# dawa_v5_5.net
KiCad netlist of a schematic drawn in EAGLE
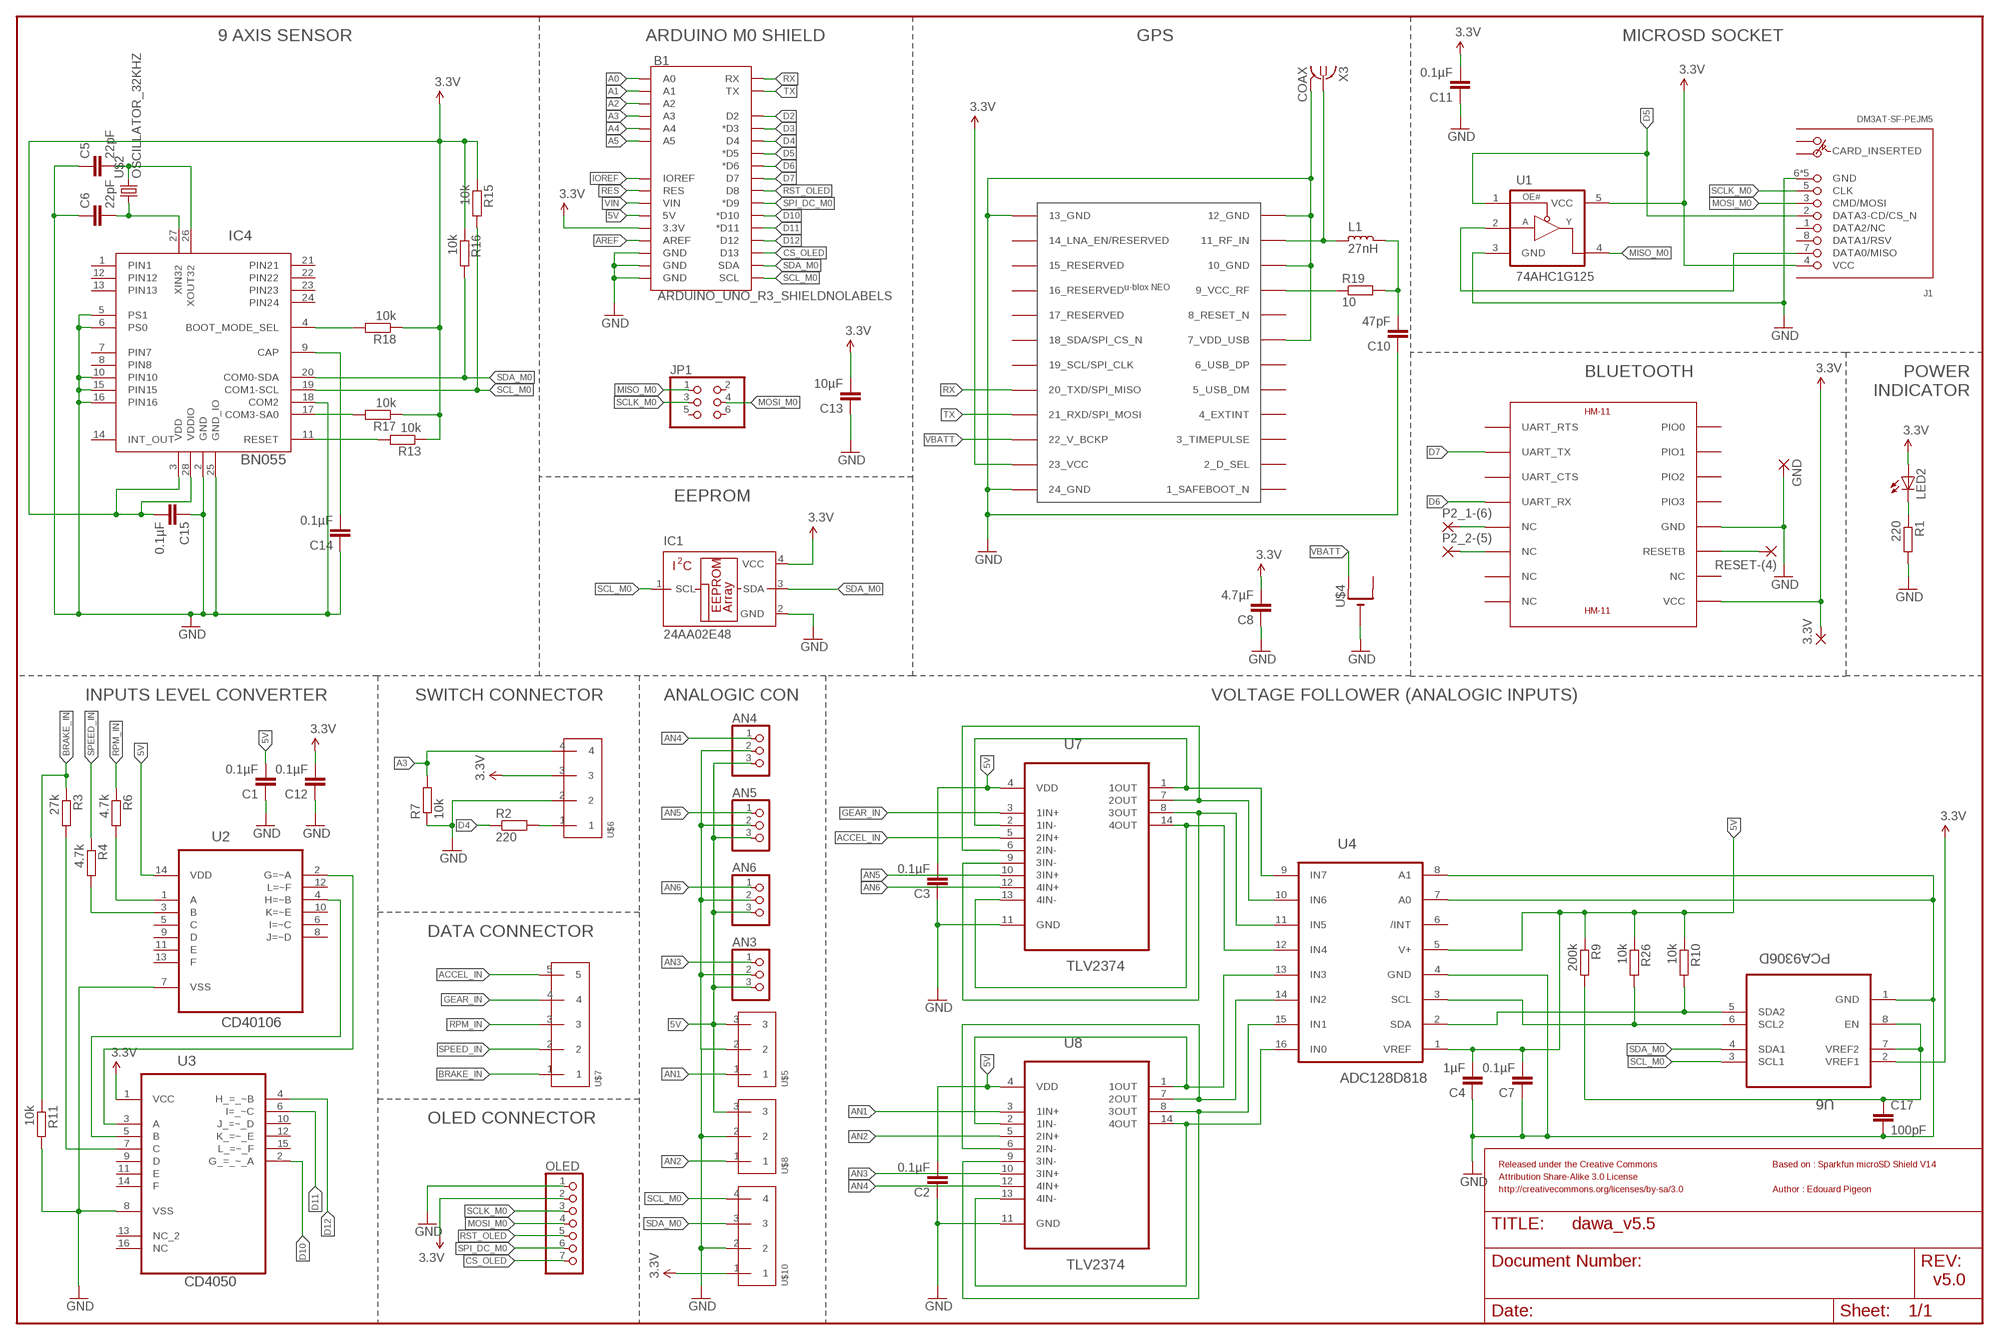
[diagram p0: schematic, sheet 1, part 1 of 2]
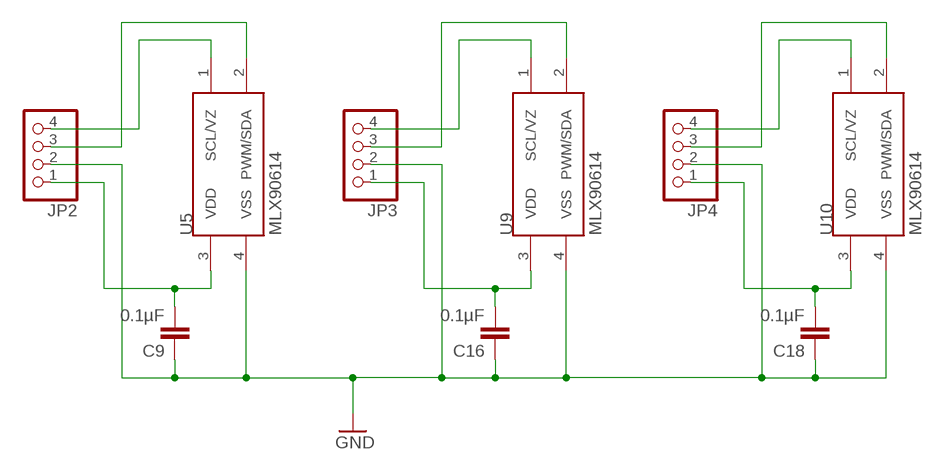
[diagram p1: schematic, sheet 1, part 2 of 2]

(export (version "E")
  (design (tool "Eeschema 10.0.6"))
  (components
    (comp (ref "3.3V")
      (value "WIREPADSMD1,27-254")
      (footprint "eagle-import:SMD1,27-2,54")
      (libsource (lib "eagle-import") (part "WIREPADSMD1,27-254"))
    )
    (comp (ref "AN3")
      (value "PINHD-1X3")
      (footprint "eagle-import:1X03")
      (libsource (lib "eagle-import") (part "PINHD-1X3"))
    )
    (comp (ref "AN4")
      (value "PINHD-1X3")
      (footprint "eagle-import:1X03")
      (libsource (lib "eagle-import") (part "PINHD-1X3"))
    )
    (comp (ref "AN5")
      (value "PINHD-1X3")
      (footprint "eagle-import:1X03")
      (libsource (lib "eagle-import") (part "PINHD-1X3"))
    )
    (comp (ref "AN6")
      (value "PINHD-1X3")
      (footprint "eagle-import:1X03")
      (libsource (lib "eagle-import") (part "PINHD-1X3"))
    )
    (comp (ref "B1")
      (value "ARDUINO_UNO_R3_SHIELDNOLABELS")
      (footprint "eagle-import:UNO_R3_SHIELD_NOLABELS")
      (libsource (lib "eagle-import") (part "ARDUINO_UNO_R3_SHIELDNOLABELS"))
    )
    (comp (ref "C1")
      (value "0.1µF")
      (footprint "eagle-import:C0603")
      (libsource (lib "eagle-import") (part "C-EUC0603"))
    )
    (comp (ref "C2")
      (value "0.1µF")
      (footprint "eagle-import:C0603")
      (libsource (lib "eagle-import") (part "C-EUC0603"))
    )
    (comp (ref "C3")
      (value "0.1µF")
      (footprint "eagle-import:C0603")
      (libsource (lib "eagle-import") (part "C-EUC0603"))
    )
    (comp (ref "C4")
      (value "1µF")
      (footprint "eagle-import:C0603")
      (libsource (lib "eagle-import") (part "C-EUC0603"))
    )
    (comp (ref "C5")
      (value "22pF")
      (footprint "eagle-import:C0603")
      (libsource (lib "eagle-import") (part "C-EUC0603"))
    )
    (comp (ref "C6")
      (value "22pF")
      (footprint "eagle-import:C0603")
      (libsource (lib "eagle-import") (part "C-EUC0603"))
    )
    (comp (ref "C7")
      (value "0.1µF")
      (footprint "eagle-import:C0603")
      (libsource (lib "eagle-import") (part "C-EUC0603"))
    )
    (comp (ref "C8")
      (value "4.7µF")
      (footprint "eagle-import:C0603")
      (libsource (lib "eagle-import") (part "C-EUC0603"))
    )
    (comp (ref "C9")
      (value "0.1µF")
      (footprint "eagle-import:C0603")
      (libsource (lib "eagle-import") (part "C-EUC0603"))
    )
    (comp (ref "C10")
      (value "47pF")
      (footprint "eagle-import:C0603")
      (libsource (lib "eagle-import") (part "C-EUC0603"))
    )
    (comp (ref "C11")
      (value "0.1µF")
      (footprint "eagle-import:C0603")
      (libsource (lib "eagle-import") (part "C-EUC0603"))
    )
    (comp (ref "C12")
      (value "0.1µF")
      (footprint "eagle-import:C0603")
      (libsource (lib "eagle-import") (part "C-EUC0603"))
    )
    (comp (ref "C13")
      (value "10µF")
      (footprint "eagle-import:C0603")
      (libsource (lib "eagle-import") (part "C-EUC0603"))
    )
    (comp (ref "C14")
      (value "0.1µF")
      (footprint "eagle-import:C0603")
      (libsource (lib "eagle-import") (part "C-EUC0603"))
    )
    (comp (ref "C15")
      (value "0.1µF")
      (footprint "eagle-import:C0603")
      (libsource (lib "eagle-import") (part "C-EUC0603"))
    )
    (comp (ref "C16")
      (value "0.1µF")
      (footprint "eagle-import:C0603")
      (libsource (lib "eagle-import") (part "C-EUC0603"))
    )
    (comp (ref "C17")
      (value "100pF")
      (footprint "eagle-import:C0603")
      (libsource (lib "eagle-import") (part "C-EUC0603"))
    )
    (comp (ref "C18")
      (value "0.1µF")
      (footprint "eagle-import:C0603")
      (libsource (lib "eagle-import") (part "C-EUC0603"))
    )
    (comp (ref "GND")
      (value "WIREPADSMD1,27-254")
      (footprint "eagle-import:SMD1,27-2,54")
      (libsource (lib "eagle-import") (part "WIREPADSMD1,27-254"))
    )
    (comp (ref "IC1")
      (value "24AA02E48")
      (footprint "eagle-import:SOT23-5L")
      (fields (field (name "MF") "MICROCHIP") (field (name "MPN") "24AA00T-I/OTG"))
      (libsource (lib "eagle-import") (part "2400OTAA"))
    )
    (comp (ref "IC4")
      (value "BN055")
      (footprint "eagle-import:LGA-28_3.80X5.20_0.5")
      (fields (field (name "PART_NUMBER") "BNO055"))
      (libsource (lib "eagle-import") (part "1658_BNO055"))
    )
    (comp (ref "J1")
      (value "DM3AT-SF-PEJM5")
      (footprint "eagle-import:DM3AT-SF-PEJM5")
      (libsource (lib "eagle-import") (part "DM3AT-SF-PEJM5"))
    )
    (comp (ref "JP1")
      (value "PINHD-2X3")
      (footprint "eagle-import:2X03")
      (libsource (lib "eagle-import") (part "PINHD-2X3"))
    )
    (comp (ref "JP2")
      (value "PINHD-1X4")
      (footprint "eagle-import:1X04")
      (libsource (lib "eagle-import") (part "PINHD-1X4"))
    )
    (comp (ref "JP3")
      (value "PINHD-1X4")
      (footprint "eagle-import:1X04")
      (libsource (lib "eagle-import") (part "PINHD-1X4"))
    )
    (comp (ref "JP4")
      (value "PINHD-1X4")
      (footprint "eagle-import:1X04")
      (libsource (lib "eagle-import") (part "PINHD-1X4"))
    )
    (comp (ref "L1")
      (value "27nH")
      (footprint "eagle-import:L0603")
      (libsource (lib "eagle-import") (part "L_0603"))
    )
    (comp (ref "LED2")
      (value "LEDCHIPLED_1206")
      (footprint "eagle-import:CHIPLED_1206")
      (libsource (lib "eagle-import") (part "LEDCHIPLED_1206"))
    )
    (comp (ref "OLED")
      (value "PINHD-1X7")
      (footprint "eagle-import:1X07")
      (libsource (lib "eagle-import") (part "PINHD-1X7"))
    )
    (comp (ref "P2_1-(6)")
      (value "WIREPADSMD1,27-254")
      (footprint "eagle-import:SMD1,27-2,54")
      (libsource (lib "eagle-import") (part "WIREPADSMD1,27-254"))
    )
    (comp (ref "P2_2-(5)")
      (value "WIREPADSMD1,27-254")
      (footprint "eagle-import:SMD1,27-2,54")
      (libsource (lib "eagle-import") (part "WIREPADSMD1,27-254"))
    )
    (comp (ref "R1")
      (value "220")
      (footprint "eagle-import:R0603")
      (libsource (lib "eagle-import") (part "R-EU_R0603"))
    )
    (comp (ref "R2")
      (value "220")
      (footprint "eagle-import:R0603")
      (libsource (lib "eagle-import") (part "R-EU_R0603"))
    )
    (comp (ref "R3")
      (value "27k")
      (footprint "eagle-import:R0603")
      (libsource (lib "eagle-import") (part "R-EU_R0603"))
    )
    (comp (ref "R4")
      (value "4.7k")
      (footprint "eagle-import:R0603")
      (libsource (lib "eagle-import") (part "R-EU_R0603"))
    )
    (comp (ref "R6")
      (value "4.7k")
      (footprint "eagle-import:R0603")
      (libsource (lib "eagle-import") (part "R-EU_R0603"))
    )
    (comp (ref "R7")
      (value "10k")
      (footprint "eagle-import:R0603")
      (libsource (lib "eagle-import") (part "R-EU_R0603"))
    )
    (comp (ref "R9")
      (value "200k")
      (footprint "eagle-import:R0603")
      (libsource (lib "eagle-import") (part "R-EU_R0603"))
    )
    (comp (ref "R10")
      (value "10k")
      (footprint "eagle-import:R0603")
      (libsource (lib "eagle-import") (part "R-EU_R0603"))
    )
    (comp (ref "R11")
      (value "10k")
      (footprint "eagle-import:R0603")
      (libsource (lib "eagle-import") (part "R-EU_R0603"))
    )
    (comp (ref "R13")
      (value "10k")
      (footprint "eagle-import:R0603")
      (libsource (lib "eagle-import") (part "R-EU_R0603"))
    )
    (comp (ref "R15")
      (value "10k")
      (footprint "eagle-import:R0603")
      (libsource (lib "eagle-import") (part "R-EU_R0603"))
    )
    (comp (ref "R16")
      (value "10k")
      (footprint "eagle-import:R0603")
      (libsource (lib "eagle-import") (part "R-EU_R0603"))
    )
    (comp (ref "R17")
      (value "10k")
      (footprint "eagle-import:R0603")
      (libsource (lib "eagle-import") (part "R-EU_R0603"))
    )
    (comp (ref "R18")
      (value "10k")
      (footprint "eagle-import:R0603")
      (libsource (lib "eagle-import") (part "R-EU_R0603"))
    )
    (comp (ref "R19")
      (value "10")
      (footprint "eagle-import:M1206")
      (libsource (lib "eagle-import") (part "R-EU_M1206"))
    )
    (comp (ref "R26")
      (value "10k")
      (footprint "eagle-import:R0603")
      (libsource (lib "eagle-import") (part "R-EU_R0603"))
    )
    (comp (ref "RESET-(4)")
      (value "WIREPADSMD1,27-254")
      (footprint "eagle-import:SMD1,27-2,54")
      (libsource (lib "eagle-import") (part "WIREPADSMD1,27-254"))
    )
    (comp (ref "U$1")
      (value "HM-11")
      (footprint "eagle-import:HM-11")
      (libsource (lib "eagle-import") (part "HM-11"))
    )
    (comp (ref "U$2")
      (value "OSCILLATOR_32KHZ")
      (footprint "eagle-import:OSCILLATOR_SMD")
      (libsource (lib "eagle-import") (part "OSCILLATOR_32KHZ"))
    )
    (comp (ref "U$3")
      (value "NEO-M8")
      (footprint "eagle-import:NEO-M8")
      (libsource (lib "eagle-import") (part "NEO-M8"))
    )
    (comp (ref "U$4")
      (value "CR1220SMT")
      (footprint "eagle-import:CR1220-SMD")
      (libsource (lib "eagle-import") (part "CR1220SMT"))
    )
    (comp (ref "U$5")
      (value "3_PIN_JST-XH-SMD")
      (footprint "eagle-import:3_PIN_JST-XH-SMD")
      (libsource (lib "eagle-import") (part "3_PIN_JST-XH-SMD"))
    )
    (comp (ref "U$6")
      (value "4_PIN_JST-XH-SMD")
      (footprint "eagle-import:4_PIN_JST-XH-SMD")
      (libsource (lib "eagle-import") (part "4_PIN_JST-XH-SMD"))
    )
    (comp (ref "U$7")
      (value "5_PIN_JST-XH-SMD")
      (footprint "eagle-import:5_PIN_JST-XH-SMD")
      (libsource (lib "eagle-import") (part "5_PIN_JST-XH-SMD"))
    )
    (comp (ref "U$8")
      (value "3_PIN_JST-XH-SMD")
      (footprint "eagle-import:3_PIN_JST-XH-SMD")
      (libsource (lib "eagle-import") (part "3_PIN_JST-XH-SMD"))
    )
    (comp (ref "U$10")
      (value "4_PIN_JST-XH-SMD")
      (footprint "eagle-import:4_PIN_JST-XH-SMD")
      (libsource (lib "eagle-import") (part "4_PIN_JST-XH-SMD"))
    )
    (comp (ref "U1")
      (value "74AHC1G125")
      (footprint "eagle-import:SOT23-5")
      (libsource (lib "eagle-import") (part "74AHC1G125DBV"))
    )
    (comp (ref "U2")
      (value "CD40106")
      (footprint "eagle-import:SOP65P640X120-14N")
      (fields (field (name "MPN") "CD40106BPW"))
      (libsource (lib "eagle-import") (part "CD40106BPW"))
    )
    (comp (ref "U3")
      (value "CD4050")
      (footprint "eagle-import:SOP65P640X120-16N")
      (fields (field (name "MPN") "CD4049UBPW"))
      (libsource (lib "eagle-import") (part "CD4049UBPW"))
    )
    (comp (ref "U4")
      (value "ADC128D818")
      (footprint "eagle-import:SOP65P640X120-16N")
      (libsource (lib "eagle-import") (part "ADC128D818"))
    )
    (comp (ref "U5")
      (value "MLX90614")
      (footprint "eagle-import:TO-39")
      (libsource (lib "eagle-import") (part "MLX90614_"))
    )
    (comp (ref "U6")
      (value "PCA9306D")
      (footprint "eagle-import:SOP50P310X90-8N")
      (fields (field (name "MPN") "PCA9306DCUT"))
      (libsource (lib "eagle-import") (part "PCA9306DCUT"))
    )
    (comp (ref "U7")
      (value "TLV2374")
      (footprint "eagle-import:SOP65P640X120-14N")
      (fields (field (name "MPN") "TLV2374IPWR"))
      (libsource (lib "eagle-import") (part "TLV2374IPWR"))
    )
    (comp (ref "U8")
      (value "TLV2374")
      (footprint "eagle-import:SOP65P640X120-14N")
      (fields (field (name "MPN") "TLV2374IPWR"))
      (libsource (lib "eagle-import") (part "TLV2374IPWR"))
    )
    (comp (ref "U9")
      (value "MLX90614")
      (footprint "eagle-import:TO-39")
      (libsource (lib "eagle-import") (part "MLX90614_"))
    )
    (comp (ref "U10")
      (value "MLX90614")
      (footprint "eagle-import:TO-39")
      (libsource (lib "eagle-import") (part "MLX90614_"))
    )
    (comp (ref "X3")
      (value "COAX")
      (footprint "eagle-import:MMCX-J-P-X-ST-EM1-MKT")
      (libsource (lib "eagle-import") (part "COAX"))
    )
  )
  (nets
    (net (code "1") (name "3.3V") (class "Default")
      (node (ref "3.3V") (pin "1") (pinfunction "P_1") (pintype "passive"))
      (node (ref "B1") (pin "3.3V") (pinfunction "3.3V_3.3V") (pintype "bidirectional"))
      (node (ref "C11") (pin "2") (pinfunction "2_2") (pintype "passive"))
      (node (ref "C12") (pin "2") (pinfunction "2_2") (pintype "passive"))
      (node (ref "C13") (pin "2") (pinfunction "2_2") (pintype "passive"))
      (node (ref "C15") (pin "2") (pinfunction "2_2") (pintype "passive"))
      (node (ref "C8") (pin "2") (pinfunction "2_2") (pintype "passive"))
      (node (ref "IC1") (pin "4") (pinfunction "VCC_4") (pintype "power_in"))
      (node (ref "IC4") (pin "28") (pinfunction "VDDIO_28") (pintype "power_in"))
      (node (ref "IC4") (pin "3") (pinfunction "VDD_3") (pintype "power_in"))
      (node (ref "J1") (pin "4") (pinfunction "VCC_4") (pintype "bidirectional"))
      (node (ref "LED2") (pin "A") (pinfunction "A_A") (pintype "passive"))
      (node (ref "OLED") (pin "2") (pinfunction "2_2") (pintype "passive"))
      (node (ref "R13") (pin "1") (pinfunction "1_1") (pintype "passive"))
      (node (ref "R15") (pin "1") (pinfunction "1_1") (pintype "passive"))
      (node (ref "R16") (pin "1") (pinfunction "1_1") (pintype "passive"))
      (node (ref "R17") (pin "1") (pinfunction "1_1") (pintype "passive"))
      (node (ref "R18") (pin "1") (pinfunction "1_1") (pintype "passive"))
      (node (ref "U$1") (pin "VCC") (pinfunction "VCC_VCC") (pintype "bidirectional"))
      (node (ref "U$10") (pin "1") (pinfunction "1_1") (pintype "bidirectional"))
      (node (ref "U$3") (pin "23") (pinfunction "23_VCC_23") (pintype "bidirectional"))
      (node (ref "U$6") (pin "3") (pinfunction "3_3") (pintype "bidirectional"))
      (node (ref "U1") (pin "5") (pinfunction "VCC_5") (pintype "power_in"))
      (node (ref "U3") (pin "1") (pinfunction "VCC_1") (pintype "power_in"))
      (node (ref "U6") (pin "2") (pinfunction "VREF1_2") (pintype "power_in"))
    )
    (net (code "2") (name "5V") (class "Default")
      (node (ref "AN3") (pin "3") (pinfunction "3_3") (pintype "passive"))
      (node (ref "AN4") (pin "3") (pinfunction "3_3") (pintype "passive"))
      (node (ref "AN5") (pin "3") (pinfunction "3_3") (pintype "passive"))
      (node (ref "AN6") (pin "3") (pinfunction "3_3") (pintype "passive"))
      (node (ref "B1") (pin "5V") (pinfunction "5V_5V") (pintype "bidirectional"))
      (node (ref "C1") (pin "2") (pinfunction "2_2") (pintype "passive"))
      (node (ref "C2") (pin "2") (pinfunction "2_2") (pintype "passive"))
      (node (ref "C3") (pin "2") (pinfunction "2_2") (pintype "passive"))
      (node (ref "C4") (pin "2") (pinfunction "2_2") (pintype "passive"))
      (node (ref "C7") (pin "2") (pinfunction "2_2") (pintype "passive"))
      (node (ref "R10") (pin "1") (pinfunction "1_1") (pintype "passive"))
      (node (ref "R26") (pin "1") (pinfunction "1_1") (pintype "passive"))
      (node (ref "R9") (pin "1") (pinfunction "1_1") (pintype "passive"))
      (node (ref "U$5") (pin "3") (pinfunction "3_3") (pintype "bidirectional"))
      (node (ref "U$8") (pin "3") (pinfunction "3_3") (pintype "bidirectional"))
      (node (ref "U2") (pin "14") (pinfunction "VDD_14") (pintype "power_in"))
      (node (ref "U4") (pin "1") (pinfunction "VREF_1") (pintype "power_in"))
      (node (ref "U4") (pin "5") (pinfunction "V+_5") (pintype "bidirectional"))
      (node (ref "U7") (pin "4") (pinfunction "VDD_4") (pintype "power_in"))
      (node (ref "U8") (pin "4") (pinfunction "VDD_4") (pintype "power_in"))
    )
    (net (code "3") (name "A0") (class "Default")
      (node (ref "B1") (pin "A0") (pinfunction "A0_A0") (pintype "bidirectional"))
    )
    (net (code "4") (name "A1") (class "Default")
      (node (ref "B1") (pin "A1") (pinfunction "A1_A1") (pintype "bidirectional"))
    )
    (net (code "5") (name "A2") (class "Default")
      (node (ref "B1") (pin "A2") (pinfunction "A2_A2") (pintype "bidirectional"))
    )
    (net (code "6") (name "A3") (class "Default")
      (node (ref "B1") (pin "A3") (pinfunction "A3_A3") (pintype "bidirectional"))
      (node (ref "R7") (pin "2") (pinfunction "2_2") (pintype "passive"))
      (node (ref "U$6") (pin "4") (pinfunction "4_4") (pintype "bidirectional"))
    )
    (net (code "7") (name "A4") (class "Default")
      (node (ref "B1") (pin "A4") (pinfunction "A4_A4") (pintype "bidirectional"))
    )
    (net (code "8") (name "A5") (class "Default")
      (node (ref "B1") (pin "A5") (pinfunction "A5_A5") (pintype "bidirectional"))
    )
    (net (code "9") (name "ACCEL_IN") (class "Default")
      (node (ref "U$7") (pin "5") (pinfunction "5_5") (pintype "bidirectional"))
      (node (ref "U7") (pin "5") (pinfunction "2IN+_5") (pintype "input"))
    )
    (net (code "10") (name "AN1") (class "Default")
      (node (ref "U$5") (pin "1") (pinfunction "1_1") (pintype "bidirectional"))
      (node (ref "U8") (pin "3") (pinfunction "1IN+_3") (pintype "input"))
    )
    (net (code "11") (name "AN2") (class "Default")
      (node (ref "U$8") (pin "1") (pinfunction "1_1") (pintype "bidirectional"))
      (node (ref "U8") (pin "5") (pinfunction "2IN+_5") (pintype "input"))
    )
    (net (code "12") (name "AN3") (class "Default")
      (node (ref "AN3") (pin "1") (pinfunction "1_1") (pintype "passive"))
      (node (ref "U8") (pin "10") (pinfunction "3IN+_10") (pintype "input"))
    )
    (net (code "13") (name "AN4") (class "Default")
      (node (ref "AN4") (pin "1") (pinfunction "1_1") (pintype "passive"))
      (node (ref "U8") (pin "12") (pinfunction "4IN+_12") (pintype "input"))
    )
    (net (code "14") (name "AN5") (class "Default")
      (node (ref "AN5") (pin "1") (pinfunction "1_1") (pintype "passive"))
      (node (ref "U7") (pin "10") (pinfunction "3IN+_10") (pintype "input"))
    )
    (net (code "15") (name "AN6") (class "Default")
      (node (ref "AN6") (pin "1") (pinfunction "1_1") (pintype "passive"))
      (node (ref "U7") (pin "12") (pinfunction "4IN+_12") (pintype "input"))
    )
    (net (code "16") (name "AREF") (class "Default")
      (node (ref "B1") (pin "AREF") (pinfunction "AREF_AREF") (pintype "bidirectional"))
    )
    (net (code "17") (name "BRAKE_IN") (class "Default")
      (node (ref "R11") (pin "1") (pinfunction "1_1") (pintype "passive"))
      (node (ref "R3") (pin "1") (pinfunction "1_1") (pintype "passive"))
      (node (ref "U$7") (pin "1") (pinfunction "1_1") (pintype "bidirectional"))
    )
    (net (code "18") (name "CS_OLED") (class "Default")
      (node (ref "B1") (pin "D13") (pinfunction "D13_D13") (pintype "bidirectional"))
      (node (ref "OLED") (pin "7") (pinfunction "7_7") (pintype "passive"))
    )
    (net (code "19") (name "D2") (class "Default")
      (node (ref "B1") (pin "D2") (pinfunction "D2_D2") (pintype "bidirectional"))
    )
    (net (code "20") (name "D3") (class "Default")
      (node (ref "B1") (pin "D3") (pinfunction "*D3_D3") (pintype "bidirectional"))
    )
    (net (code "21") (name "D4") (class "Default")
      (node (ref "B1") (pin "D4") (pinfunction "D4_D4") (pintype "bidirectional"))
      (node (ref "R2") (pin "1") (pinfunction "1_1") (pintype "passive"))
    )
    (net (code "22") (name "D5") (class "Default")
      (node (ref "B1") (pin "D5") (pinfunction "*D5_D5") (pintype "bidirectional"))
      (node (ref "J1") (pin "2") (pinfunction "DATA3-CD/CS_N_2") (pintype "bidirectional"))
      (node (ref "U1") (pin "1") (pinfunction "OE#_1") (pintype "input"))
    )
    (net (code "23") (name "D6") (class "Default")
      (node (ref "B1") (pin "D6") (pinfunction "*D6_D6") (pintype "bidirectional"))
      (node (ref "U$1") (pin "UART_RX") (pinfunction "UART_RX_UART_RX") (pintype "bidirectional"))
    )
    (net (code "24") (name "D7") (class "Default")
      (node (ref "B1") (pin "D7") (pinfunction "D7_D7") (pintype "bidirectional"))
      (node (ref "U$1") (pin "UART_TX") (pinfunction "UART_TX_UART_TX") (pintype "bidirectional"))
    )
    (net (code "25") (name "D10") (class "Default")
      (node (ref "B1") (pin "D10") (pinfunction "*D10_D10") (pintype "bidirectional"))
      (node (ref "U3") (pin "2") (pinfunction "G_=_~{_A}_2") (pintype "output"))
    )
    (net (code "26") (name "D11") (class "Default")
      (node (ref "B1") (pin "D11") (pinfunction "*D11_D11") (pintype "bidirectional"))
      (node (ref "U3") (pin "6") (pinfunction "I=_~{C}_6") (pintype "output"))
    )
    (net (code "27") (name "D12") (class "Default")
      (node (ref "B1") (pin "D12") (pinfunction "D12_D12") (pintype "bidirectional"))
      (node (ref "U3") (pin "4") (pinfunction "H_=_~{B}_4") (pintype "output"))
    )
    (net (code "28") (name "GEAR_IN") (class "Default")
      (node (ref "U$7") (pin "4") (pinfunction "4_4") (pintype "bidirectional"))
      (node (ref "U7") (pin "3") (pinfunction "1IN+_3") (pintype "input"))
    )
    (net (code "29") (name "GND") (class "Default")
      (node (ref "AN3") (pin "2") (pinfunction "2_2") (pintype "passive"))
      (node (ref "AN4") (pin "2") (pinfunction "2_2") (pintype "passive"))
      (node (ref "AN5") (pin "2") (pinfunction "2_2") (pintype "passive"))
      (node (ref "AN6") (pin "2") (pinfunction "2_2") (pintype "passive"))
      (node (ref "B1") (pin "GND@0") (pinfunction "GND_GND@0") (pintype "bidirectional"))
      (node (ref "B1") (pin "GND@1") (pinfunction "GND_GND@1") (pintype "bidirectional"))
      (node (ref "B1") (pin "GND@2") (pinfunction "GND_GND@2") (pintype "bidirectional"))
      (node (ref "C1") (pin "1") (pinfunction "1_1") (pintype "passive"))
      (node (ref "C10") (pin "1") (pinfunction "1_1") (pintype "passive"))
      (node (ref "C11") (pin "1") (pinfunction "1_1") (pintype "passive"))
      (node (ref "C12") (pin "1") (pinfunction "1_1") (pintype "passive"))
      (node (ref "C13") (pin "1") (pinfunction "1_1") (pintype "passive"))
      (node (ref "C14") (pin "1") (pinfunction "1_1") (pintype "passive"))
      (node (ref "C15") (pin "1") (pinfunction "1_1") (pintype "passive"))
      (node (ref "C16") (pin "1") (pinfunction "1_1") (pintype "passive"))
      (node (ref "C17") (pin "2") (pinfunction "2_2") (pintype "passive"))
      (node (ref "C18") (pin "1") (pinfunction "1_1") (pintype "passive"))
      (node (ref "C2") (pin "1") (pinfunction "1_1") (pintype "passive"))
      (node (ref "C3") (pin "1") (pinfunction "1_1") (pintype "passive"))
      (node (ref "C4") (pin "1") (pinfunction "1_1") (pintype "passive"))
      (node (ref "C5") (pin "1") (pinfunction "1_1") (pintype "passive"))
      (node (ref "C6") (pin "1") (pinfunction "1_1") (pintype "passive"))
      (node (ref "C7") (pin "1") (pinfunction "1_1") (pintype "passive"))
      (node (ref "C8") (pin "1") (pinfunction "1_1") (pintype "passive"))
      (node (ref "C9") (pin "1") (pinfunction "1_1") (pintype "passive"))
      (node (ref "GND") (pin "1") (pinfunction "P_1") (pintype "passive"))
      (node (ref "IC1") (pin "2") (pinfunction "GND_2") (pintype "power_in"))
      (node (ref "IC4") (pin "10") (pinfunction "PIN10_10") (pintype "passive"))
      (node (ref "IC4") (pin "15") (pinfunction "PIN15_15") (pintype "passive"))
      (node (ref "IC4") (pin "16") (pinfunction "PIN16_16") (pintype "passive"))
      (node (ref "IC4") (pin "18") (pinfunction "COM2_18") (pintype "bidirectional"))
      (node (ref "IC4") (pin "2") (pinfunction "GND_2") (pintype "power_in"))
      (node (ref "IC4") (pin "25") (pinfunction "GND_IO_25") (pintype "power_in"))
      (node (ref "IC4") (pin "5") (pinfunction "PS1_5") (pintype "input"))
      (node (ref "IC4") (pin "6") (pinfunction "PS0_6") (pintype "input"))
      (node (ref "J1") (pin "6") (pinfunction "GND_6") (pintype "bidirectional"))
      (node (ref "J1") (pin "MOUNT0") (pinfunction "GND_MOUNT0") (pintype "bidirectional"))
      (node (ref "J1") (pin "MOUNT1") (pinfunction "GND_MOUNT1") (pintype "bidirectional"))
      (node (ref "J1") (pin "MOUNT2") (pinfunction "GND_MOUNT2") (pintype "bidirectional"))
      (node (ref "J1") (pin "MOUNT3") (pinfunction "GND_MOUNT3") (pintype "bidirectional"))
      (node (ref "JP2") (pin "2") (pinfunction "2_2") (pintype "passive"))
      (node (ref "JP3") (pin "2") (pinfunction "2_2") (pintype "passive"))
      (node (ref "JP4") (pin "2") (pinfunction "2_2") (pintype "passive"))
      (node (ref "OLED") (pin "1") (pinfunction "1_1") (pintype "passive"))
      (node (ref "R1") (pin "2") (pinfunction "2_2") (pintype "passive"))
      (node (ref "R11") (pin "2") (pinfunction "2_2") (pintype "passive"))
      (node (ref "R7") (pin "1") (pinfunction "1_1") (pintype "passive"))
      (node (ref "U$1") (pin "GND") (pinfunction "GND_GND") (pintype "bidirectional"))
      (node (ref "U$10") (pin "2") (pinfunction "2_2") (pintype "bidirectional"))
      (node (ref "U$3") (pin "10") (pinfunction "10_GND_10") (pintype "bidirectional"))
      (node (ref "U$3") (pin "12") (pinfunction "12_GND_12") (pintype "bidirectional"))
      (node (ref "U$3") (pin "13") (pinfunction "13_GND_13") (pintype "bidirectional"))
      (node (ref "U$3") (pin "24") (pinfunction "24_GND_24") (pintype "bidirectional"))
      (node (ref "U$3") (pin "7") (pinfunction "7_VDD_USB_7") (pintype "bidirectional"))
      (node (ref "U$4") (pin "-") (pinfunction "-_-") (pintype "passive"))
      (node (ref "U$5") (pin "2") (pinfunction "2_2") (pintype "bidirectional"))
      (node (ref "U$6") (pin "2") (pinfunction "2_2") (pintype "bidirectional"))
      (node (ref "U$8") (pin "2") (pinfunction "2_2") (pintype "bidirectional"))
      (node (ref "U1") (pin "3") (pinfunction "GND_3") (pintype "power_in"))
      (node (ref "U10") (pin "4") (pinfunction "VSS_4") (pintype "bidirectional"))
      (node (ref "U2") (pin "7") (pinfunction "VSS_7") (pintype "power_in"))
      (node (ref "U3") (pin "8") (pinfunction "VSS_8") (pintype "power_in"))
      (node (ref "U4") (pin "4") (pinfunction "GND_4") (pintype "bidirectional"))
      (node (ref "U4") (pin "7") (pinfunction "A0_7") (pintype "input"))
      (node (ref "U4") (pin "8") (pinfunction "A1_8") (pintype "input"))
      (node (ref "U5") (pin "4") (pinfunction "VSS_4") (pintype "bidirectional"))
      (node (ref "U6") (pin "1") (pinfunction "GND_1") (pintype "passive"))
      (node (ref "U7") (pin "11") (pinfunction "GND_11") (pintype "power_in"))
      (node (ref "U8") (pin "11") (pinfunction "GND_11") (pintype "power_in"))
      (node (ref "U9") (pin "4") (pinfunction "VSS_4") (pintype "bidirectional"))
      (node (ref "X3") (pin "2@1") (pinfunction "GND_2@1") (pintype "power_in"))
    )
    (net (code "30") (name "IOREF") (class "Default")
      (node (ref "B1") (pin "IOREF") (pinfunction "IOREF_IOREF") (pintype "bidirectional"))
    )
    (net (code "31") (name "MISO_M0") (class "Default")
      (node (ref "JP1") (pin "1") (pinfunction "1_1") (pintype "passive"))
      (node (ref "U1") (pin "4") (pinfunction "Y_4") (pintype "output"))
    )
    (net (code "32") (name "MOSI_M0") (class "Default")
      (node (ref "J1") (pin "3") (pinfunction "CMD/MOSI_3") (pintype "bidirectional"))
      (node (ref "JP1") (pin "4") (pinfunction "4_4") (pintype "passive"))
      (node (ref "OLED") (pin "4") (pinfunction "4_4") (pintype "passive"))
    )
    (net (code "33") (name "Net-(C10-Pad2)") (class "Default")
      (node (ref "C10") (pin "2") (pinfunction "2_2") (pintype "passive"))
      (node (ref "L1") (pin "1") (pinfunction "1_1") (pintype "passive"))
      (node (ref "R19") (pin "2") (pinfunction "2_2") (pintype "passive"))
    )
    (net (code "34") (name "Net-(IC4-BOOT_MODE_SEL)") (class "Default")
      (node (ref "IC4") (pin "4") (pinfunction "BOOT_MODE_SEL_4") (pintype "input"))
      (node (ref "R18") (pin "2") (pinfunction "2_2") (pintype "passive"))
    )
    (net (code "35") (name "Net-(IC4-CAP)") (class "Default")
      (node (ref "C14") (pin "2") (pinfunction "2_2") (pintype "passive"))
      (node (ref "IC4") (pin "9") (pinfunction "CAP_9") (pintype "tri_state"))
    )
    (net (code "36") (name "Net-(IC4-COM3-SA0)") (class "Default")
      (node (ref "IC4") (pin "17") (pinfunction "COM3-SA0_17") (pintype "bidirectional"))
      (node (ref "R17") (pin "2") (pinfunction "2_2") (pintype "passive"))
    )
    (net (code "37") (name "Net-(IC4-RESET)") (class "Default")
      (node (ref "IC4") (pin "11") (pinfunction "RESET_11") (pintype "input"))
      (node (ref "R13") (pin "2") (pinfunction "2_2") (pintype "passive"))
    )
    (net (code "38") (name "Net-(IC4-XIN32)") (class "Default")
      (node (ref "C6") (pin "2") (pinfunction "2_2") (pintype "passive"))
      (node (ref "IC4") (pin "27") (pinfunction "XIN32_27") (pintype "bidirectional"))
      (node (ref "U$2") (pin "1") (pinfunction "1_1") (pintype "passive"))
    )
    (net (code "39") (name "Net-(IC4-XOUT32)") (class "Default")
      (node (ref "C5") (pin "2") (pinfunction "2_2") (pintype "passive"))
      (node (ref "IC4") (pin "26") (pinfunction "XOUT32_26") (pintype "output"))
      (node (ref "U$2") (pin "2") (pinfunction "2_2") (pintype "passive"))
    )
    (net (code "40") (name "Net-(J1-DATA0{slash}MISO)") (class "Default")
      (node (ref "J1") (pin "7") (pinfunction "DATA0/MISO_7") (pintype "bidirectional"))
      (node (ref "U1") (pin "2") (pinfunction "A_2") (pintype "input"))
    )
    (net (code "41") (name "Net-(LED2-PadC)") (class "Default")
      (node (ref "LED2") (pin "C") (pinfunction "C_C") (pintype "passive"))
      (node (ref "R1") (pin "1") (pinfunction "1_1") (pintype "passive"))
    )
    (net (code "42") (name "Net-(P2_1-(6)-P)") (class "Default")
      (node (ref "P2_1-(6)") (pin "1") (pinfunction "P_1") (pintype "passive"))
      (node (ref "U$1") (pin "NC@5") (pinfunction "NC_NC@5") (pintype "bidirectional"))
    )
    (net (code "43") (name "Net-(P2_2-(5)-P)") (class "Default")
      (node (ref "P2_2-(5)") (pin "1") (pinfunction "P_1") (pintype "passive"))
      (node (ref "U$1") (pin "NC@6") (pinfunction "NC_NC@6") (pintype "bidirectional"))
    )
    (net (code "44") (name "Net-(R2-Pad2)") (class "Default")
      (node (ref "R2") (pin "2") (pinfunction "2_2") (pintype "passive"))
      (node (ref "U$6") (pin "1") (pinfunction "1_1") (pintype "bidirectional"))
    )
    (net (code "45") (name "Net-(RESET-(4)-P)") (class "Default")
      (node (ref "RESET-(4)") (pin "1") (pinfunction "P_1") (pintype "passive"))
      (node (ref "U$1") (pin "RESETB") (pinfunction "RESETB_RESETB") (pintype "bidirectional"))
    )
    (net (code "46") (name "Net-(U$3-9_VCC_RF)") (class "Default")
      (node (ref "R19") (pin "1") (pinfunction "1_1") (pintype "passive"))
      (node (ref "U$3") (pin "9") (pinfunction "9_VCC_RF_9") (pintype "bidirectional"))
    )
    (net (code "47") (name "Net-(U$3-11_RF_IN)") (class "Default")
      (node (ref "L1") (pin "2") (pinfunction "2_2") (pintype "passive"))
      (node (ref "U$3") (pin "11") (pinfunction "11_RF_IN_11") (pintype "bidirectional"))
      (node (ref "X3") (pin "1") (pinfunction "1_1") (pintype "passive"))
    )
    (net (code "48") (name "Net-(U2-A)") (class "Default")
      (node (ref "R6") (pin "2") (pinfunction "2_2") (pintype "passive"))
      (node (ref "U2") (pin "1") (pinfunction "A_1") (pintype "input"))
    )
    (net (code "49") (name "Net-(U2-B)") (class "Default")
      (node (ref "R4") (pin "2") (pinfunction "2_2") (pintype "passive"))
      (node (ref "U2") (pin "3") (pinfunction "B_3") (pintype "input"))
    )
    (net (code "50") (name "Net-(U2-G=~{A})") (class "Default")
      (node (ref "U2") (pin "2") (pinfunction "G=~{A}_2") (pintype "output"))
      (node (ref "U3") (pin "3") (pinfunction "A_3") (pintype "input"))
    )
    (net (code "51") (name "Net-(U2-H=~{B})") (class "Default")
      (node (ref "U2") (pin "4") (pinfunction "H=~{B}_4") (pintype "output"))
      (node (ref "U3") (pin "5") (pinfunction "B_5") (pintype "input"))
    )
    (net (code "52") (name "Net-(U3-C)") (class "Default")
      (node (ref "R3") (pin "2") (pinfunction "2_2") (pintype "passive"))
      (node (ref "U3") (pin "7") (pinfunction "C_7") (pintype "input"))
    )
    (net (code "53") (name "Net-(U4-IN0)") (class "Default")
      (node (ref "U4") (pin "16") (pinfunction "IN0_16") (pintype "input"))
      (node (ref "U8") (pin "13") (pinfunction "4IN-_13") (pintype "input"))
      (node (ref "U8") (pin "14") (pinfunction "4OUT_14") (pintype "output"))
    )
    (net (code "54") (name "Net-(U4-IN1)") (class "Default")
      (node (ref "U4") (pin "15") (pinfunction "IN1_15") (pintype "input"))
      (node (ref "U8") (pin "8") (pinfunction "3OUT_8") (pintype "output"))
      (node (ref "U8") (pin "9") (pinfunction "3IN-_9") (pintype "input"))
    )
    (net (code "55") (name "Net-(U4-IN2)") (class "Default")
      (node (ref "U4") (pin "14") (pinfunction "IN2_14") (pintype "input"))
      (node (ref "U8") (pin "6") (pinfunction "2IN-_6") (pintype "input"))
      (node (ref "U8") (pin "7") (pinfunction "2OUT_7") (pintype "output"))
    )
    (net (code "56") (name "Net-(U4-IN3)") (class "Default")
      (node (ref "U4") (pin "13") (pinfunction "IN3_13") (pintype "input"))
      (node (ref "U8") (pin "1") (pinfunction "1OUT_1") (pintype "output"))
      (node (ref "U8") (pin "2") (pinfunction "1IN-_2") (pintype "input"))
    )
    (net (code "57") (name "Net-(U4-IN4)") (class "Default")
      (node (ref "U4") (pin "12") (pinfunction "IN4_12") (pintype "input"))
      (node (ref "U7") (pin "13") (pinfunction "4IN-_13") (pintype "input"))
      (node (ref "U7") (pin "14") (pinfunction "4OUT_14") (pintype "output"))
    )
    (net (code "58") (name "Net-(U4-IN5)") (class "Default")
      (node (ref "U4") (pin "11") (pinfunction "IN5_11") (pintype "input"))
      (node (ref "U7") (pin "8") (pinfunction "3OUT_8") (pintype "output"))
      (node (ref "U7") (pin "9") (pinfunction "3IN-_9") (pintype "input"))
    )
    (net (code "59") (name "Net-(U4-IN6)") (class "Default")
      (node (ref "U4") (pin "10") (pinfunction "IN6_10") (pintype "input"))
      (node (ref "U7") (pin "6") (pinfunction "2IN-_6") (pintype "input"))
      (node (ref "U7") (pin "7") (pinfunction "2OUT_7") (pintype "output"))
    )
    (net (code "60") (name "Net-(U4-IN7)") (class "Default")
      (node (ref "U4") (pin "9") (pinfunction "IN7_9") (pintype "input"))
      (node (ref "U7") (pin "1") (pinfunction "1OUT_1") (pintype "output"))
      (node (ref "U7") (pin "2") (pinfunction "1IN-_2") (pintype "input"))
    )
    (net (code "61") (name "Net-(U4-SCL)") (class "Default")
      (node (ref "R26") (pin "2") (pinfunction "2_2") (pintype "passive"))
      (node (ref "U4") (pin "3") (pinfunction "SCL_3") (pintype "bidirectional"))
      (node (ref "U6") (pin "6") (pinfunction "SCL2_6") (pintype "bidirectional"))
    )
    (net (code "62") (name "Net-(U4-SDA)") (class "Default")
      (node (ref "R10") (pin "2") (pinfunction "2_2") (pintype "passive"))
      (node (ref "U4") (pin "2") (pinfunction "SDA_2") (pintype "bidirectional"))
      (node (ref "U6") (pin "5") (pinfunction "SDA2_5") (pintype "bidirectional"))
    )
    (net (code "63") (name "Net-(U5-PWM{slash}SDA)") (class "Default")
      (node (ref "JP2") (pin "3") (pinfunction "3_3") (pintype "passive"))
      (node (ref "U5") (pin "2") (pinfunction "PWM/SDA_2") (pintype "bidirectional"))
    )
    (net (code "64") (name "Net-(U5-SCL{slash}VZ)") (class "Default")
      (node (ref "JP2") (pin "4") (pinfunction "4_4") (pintype "passive"))
      (node (ref "U5") (pin "1") (pinfunction "SCL/VZ_1") (pintype "bidirectional"))
    )
    (net (code "65") (name "Net-(U5-VDD)") (class "Default")
      (node (ref "C9") (pin "2") (pinfunction "2_2") (pintype "passive"))
      (node (ref "JP2") (pin "1") (pinfunction "1_1") (pintype "passive"))
      (node (ref "U5") (pin "3") (pinfunction "VDD_3") (pintype "bidirectional"))
    )
    (net (code "66") (name "Net-(U6-EN)") (class "Default")
      (node (ref "C17") (pin "1") (pinfunction "1_1") (pintype "passive"))
      (node (ref "R9") (pin "2") (pinfunction "2_2") (pintype "passive"))
      (node (ref "U6") (pin "7") (pinfunction "VREF2_7") (pintype "power_in"))
      (node (ref "U6") (pin "8") (pinfunction "EN_8") (pintype "input"))
    )
    (net (code "67") (name "Net-(U9-PWM{slash}SDA)") (class "Default")
      (node (ref "JP3") (pin "3") (pinfunction "3_3") (pintype "passive"))
      (node (ref "U9") (pin "2") (pinfunction "PWM/SDA_2") (pintype "bidirectional"))
    )
    (net (code "68") (name "Net-(U9-SCL{slash}VZ)") (class "Default")
      (node (ref "JP3") (pin "4") (pinfunction "4_4") (pintype "passive"))
      (node (ref "U9") (pin "1") (pinfunction "SCL/VZ_1") (pintype "bidirectional"))
    )
    (net (code "69") (name "Net-(U9-VDD)") (class "Default")
      (node (ref "C16") (pin "2") (pinfunction "2_2") (pintype "passive"))
      (node (ref "JP3") (pin "1") (pinfunction "1_1") (pintype "passive"))
      (node (ref "U9") (pin "3") (pinfunction "VDD_3") (pintype "bidirectional"))
    )
    (net (code "70") (name "Net-(U10-PWM{slash}SDA)") (class "Default")
      (node (ref "JP4") (pin "3") (pinfunction "3_3") (pintype "passive"))
      (node (ref "U10") (pin "2") (pinfunction "PWM/SDA_2") (pintype "bidirectional"))
    )
    (net (code "71") (name "Net-(U10-SCL{slash}VZ)") (class "Default")
      (node (ref "JP4") (pin "4") (pinfunction "4_4") (pintype "passive"))
      (node (ref "U10") (pin "1") (pinfunction "SCL/VZ_1") (pintype "bidirectional"))
    )
    (net (code "72") (name "Net-(U10-VDD)") (class "Default")
      (node (ref "C18") (pin "2") (pinfunction "2_2") (pintype "passive"))
      (node (ref "JP4") (pin "1") (pinfunction "1_1") (pintype "passive"))
      (node (ref "U10") (pin "3") (pinfunction "VDD_3") (pintype "bidirectional"))
    )
    (net (code "73") (name "RES") (class "Default")
      (node (ref "B1") (pin "RES") (pinfunction "RES_RES") (pintype "bidirectional"))
    )
    (net (code "74") (name "RPM_IN") (class "Default")
      (node (ref "R6") (pin "1") (pinfunction "1_1") (pintype "passive"))
      (node (ref "U$7") (pin "3") (pinfunction "3_3") (pintype "bidirectional"))
    )
    (net (code "75") (name "RST_OLED") (class "Default")
      (node (ref "B1") (pin "D8") (pinfunction "D8_D8") (pintype "bidirectional"))
      (node (ref "OLED") (pin "5") (pinfunction "5_5") (pintype "passive"))
    )
    (net (code "76") (name "RX") (class "Default")
      (node (ref "B1") (pin "RX") (pinfunction "RX_RX") (pintype "bidirectional"))
      (node (ref "U$3") (pin "20") (pinfunction "20_TXD/SPI_MISO_20") (pintype "bidirectional"))
    )
    (net (code "77") (name "SCLK_M0") (class "Default")
      (node (ref "J1") (pin "5") (pinfunction "CLK_5") (pintype "bidirectional"))
      (node (ref "JP1") (pin "3") (pinfunction "3_3") (pintype "passive"))
      (node (ref "OLED") (pin "3") (pinfunction "3_3") (pintype "passive"))
    )
    (net (code "78") (name "SCL_M0") (class "Default")
      (node (ref "B1") (pin "SCL") (pinfunction "SCL_SCL") (pintype "bidirectional"))
      (node (ref "IC1") (pin "1") (pinfunction "SCL_1") (pintype "input"))
      (node (ref "IC4") (pin "19") (pinfunction "COM1-SCL_19") (pintype "bidirectional"))
      (node (ref "R15") (pin "2") (pinfunction "2_2") (pintype "passive"))
      (node (ref "U$10") (pin "4") (pinfunction "4_4") (pintype "bidirectional"))
      (node (ref "U6") (pin "3") (pinfunction "SCL1_3") (pintype "bidirectional"))
    )
    (net (code "79") (name "SDA_M0") (class "Default")
      (node (ref "B1") (pin "SDA") (pinfunction "SDA_SDA") (pintype "bidirectional"))
      (node (ref "IC1") (pin "3") (pinfunction "SDA_3") (pintype "bidirectional"))
      (node (ref "IC4") (pin "20") (pinfunction "COM0-SDA_20") (pintype "bidirectional"))
      (node (ref "R16") (pin "2") (pinfunction "2_2") (pintype "passive"))
      (node (ref "U$10") (pin "3") (pinfunction "3_3") (pintype "bidirectional"))
      (node (ref "U6") (pin "4") (pinfunction "SDA1_4") (pintype "bidirectional"))
    )
    (net (code "80") (name "SPEED_IN") (class "Default")
      (node (ref "R4") (pin "1") (pinfunction "1_1") (pintype "passive"))
      (node (ref "U$7") (pin "2") (pinfunction "2_2") (pintype "bidirectional"))
    )
    (net (code "81") (name "SPI_DC_M0") (class "Default")
      (node (ref "B1") (pin "D9") (pinfunction "*D9_D9") (pintype "bidirectional"))
      (node (ref "OLED") (pin "6") (pinfunction "6_6") (pintype "passive"))
    )
    (net (code "82") (name "TX") (class "Default")
      (node (ref "B1") (pin "TX") (pinfunction "TX_TX") (pintype "bidirectional"))
      (node (ref "U$3") (pin "21") (pinfunction "21_RXD/SPI_MOSI_21") (pintype "bidirectional"))
    )
    (net (code "83") (name "VBATT") (class "Default")
      (node (ref "U$3") (pin "22") (pinfunction "22_V_BCKP_22") (pintype "bidirectional"))
      (node (ref "U$4") (pin "+$1") (pinfunction "+_+$1") (pintype "passive"))
    )
    (net (code "84") (name "VIN") (class "Default")
      (node (ref "B1") (pin "VIN") (pinfunction "VIN_VIN") (pintype "bidirectional"))
    )
    (net (code "85") (name "unconnected-(IC4-INT_OUT-Pad14)") (class "Default")
      (node (ref "IC4") (pin "14") (pinfunction "INT_OUT_14") (pintype "output"))
    )
    (net (code "86") (name "unconnected-(IC4-PIN1-Pad1)") (class "Default")
      (node (ref "IC4") (pin "1") (pinfunction "PIN1_1") (pintype "no_connect"))
    )
    (net (code "87") (name "unconnected-(IC4-PIN7-Pad7)") (class "Default")
      (node (ref "IC4") (pin "7") (pinfunction "PIN7_7") (pintype "tri_state"))
    )
    (net (code "88") (name "unconnected-(IC4-PIN8-Pad8)") (class "Default")
      (node (ref "IC4") (pin "8") (pinfunction "PIN8_8") (pintype "tri_state"))
    )
    (net (code "89") (name "unconnected-(IC4-PIN12-Pad12)") (class "Default")
      (node (ref "IC4") (pin "12") (pinfunction "PIN12_12") (pintype "passive"))
    )
    (net (code "90") (name "unconnected-(IC4-PIN13-Pad13)") (class "Default")
      (node (ref "IC4") (pin "13") (pinfunction "PIN13_13") (pintype "passive"))
    )
    (net (code "91") (name "unconnected-(IC4-PIN21-Pad21)") (class "Default")
      (node (ref "IC4") (pin "21") (pinfunction "PIN21_21") (pintype "passive"))
    )
    (net (code "92") (name "unconnected-(IC4-PIN22-Pad22)") (class "Default")
      (node (ref "IC4") (pin "22") (pinfunction "PIN22_22") (pintype "passive"))
    )
    (net (code "93") (name "unconnected-(IC4-PIN23-Pad23)") (class "Default")
      (node (ref "IC4") (pin "23") (pinfunction "PIN23_23") (pintype "passive"))
    )
    (net (code "94") (name "unconnected-(IC4-PIN24-Pad24)") (class "Default")
      (node (ref "IC4") (pin "24") (pinfunction "PIN24_24") (pintype "passive"))
    )
    (net (code "95") (name "unconnected-(J1-DATA1{slash}RSV-Pad8)") (class "Default")
      (node (ref "J1") (pin "8") (pinfunction "DATA1/RSV_8") (pintype "bidirectional"))
    )
    (net (code "96") (name "unconnected-(J1-DATA2{slash}NC-Pad1)") (class "Default")
      (node (ref "J1") (pin "1") (pinfunction "DATA2/NC_1") (pintype "bidirectional"))
    )
    (net (code "97") (name "unconnected-(J1-PadA)") (class "Default")
      (node (ref "J1") (pin "A") (pinfunction "A_A") (pintype "bidirectional"))
    )
    (net (code "98") (name "unconnected-(J1-PadB)") (class "Default")
      (node (ref "J1") (pin "B") (pinfunction "B_B") (pintype "bidirectional"))
    )
    (net (code "99") (name "unconnected-(JP1-Pad2)") (class "Default")
      (node (ref "JP1") (pin "2") (pinfunction "2_2") (pintype "passive"))
    )
    (net (code "100") (name "unconnected-(JP1-Pad5)") (class "Default")
      (node (ref "JP1") (pin "5") (pinfunction "5_5") (pintype "passive"))
    )
    (net (code "101") (name "unconnected-(JP1-Pad6)") (class "Default")
      (node (ref "JP1") (pin "6") (pinfunction "6_6") (pintype "passive"))
    )
    (net (code "102") (name "unconnected-(U$1-NC-PadNC@7)") (class "Default")
      (node (ref "U$1") (pin "NC@7") (pinfunction "NC_NC@7") (pintype "bidirectional"))
    )
    (net (code "103") (name "unconnected-(U$1-NC-PadNC@8)") (class "Default")
      (node (ref "U$1") (pin "NC@8") (pinfunction "NC_NC@8") (pintype "bidirectional"))
    )
    (net (code "104") (name "unconnected-(U$1-NC-PadNC@10)") (class "Default")
      (node (ref "U$1") (pin "NC@10") (pinfunction "NC_NC@10") (pintype "bidirectional"))
    )
    (net (code "105") (name "unconnected-(U$1-PadPIO0)") (class "Default")
      (node (ref "U$1") (pin "PIO0") (pinfunction "PIO0_PIO0") (pintype "bidirectional"))
    )
    (net (code "106") (name "unconnected-(U$1-PadPIO1)") (class "Default")
      (node (ref "U$1") (pin "PIO1") (pinfunction "PIO1_PIO1") (pintype "bidirectional"))
    )
    (net (code "107") (name "unconnected-(U$1-PadPIO2)") (class "Default")
      (node (ref "U$1") (pin "PIO2") (pinfunction "PIO2_PIO2") (pintype "bidirectional"))
    )
    (net (code "108") (name "unconnected-(U$1-PadPIO3)") (class "Default")
      (node (ref "U$1") (pin "PIO3") (pinfunction "PIO3_PIO3") (pintype "bidirectional"))
    )
    (net (code "109") (name "unconnected-(U$1-PadUART_CTS)") (class "Default")
      (node (ref "U$1") (pin "UART_CTS") (pinfunction "UART_CTS_UART_CTS") (pintype "bidirectional"))
    )
    (net (code "110") (name "unconnected-(U$1-PadUART_RTS)") (class "Default")
      (node (ref "U$1") (pin "UART_RTS") (pinfunction "UART_RTS_UART_RTS") (pintype "bidirectional"))
    )
    (net (code "111") (name "unconnected-(U$3-1_SAFEBOOT_N-Pad1)") (class "Default")
      (node (ref "U$3") (pin "1") (pinfunction "1_SAFEBOOT_N_1") (pintype "bidirectional"))
    )
    (net (code "112") (name "unconnected-(U$3-2_D_SEL-Pad2)") (class "Default")
      (node (ref "U$3") (pin "2") (pinfunction "2_D_SEL_2") (pintype "bidirectional"))
    )
    (net (code "113") (name "unconnected-(U$3-3_TIMEPULSE-Pad3)") (class "Default")
      (node (ref "U$3") (pin "3") (pinfunction "3_TIMEPULSE_3") (pintype "bidirectional"))
    )
    (net (code "114") (name "unconnected-(U$3-4_EXTINT-Pad4)") (class "Default")
      (node (ref "U$3") (pin "4") (pinfunction "4_EXTINT_4") (pintype "bidirectional"))
    )
    (net (code "115") (name "unconnected-(U$3-5_USB_DM-Pad5)") (class "Default")
      (node (ref "U$3") (pin "5") (pinfunction "5_USB_DM_5") (pintype "bidirectional"))
    )
    (net (code "116") (name "unconnected-(U$3-6_USB_DP-Pad6)") (class "Default")
      (node (ref "U$3") (pin "6") (pinfunction "6_USB_DP_6") (pintype "bidirectional"))
    )
    (net (code "117") (name "unconnected-(U$3-8_RESET_N-Pad8)") (class "Default")
      (node (ref "U$3") (pin "8") (pinfunction "8_RESET_N_8") (pintype "bidirectional"))
    )
    (net (code "118") (name "unconnected-(U$3-14_LNA_EN{slash}RESERVED-Pad14)") (class "Default")
      (node (ref "U$3") (pin "14") (pinfunction "14_LNA_EN/RESERVED_14") (pintype "bidirectional"))
    )
    (net (code "119") (name "unconnected-(U$3-15_RESERVED-Pad15)") (class "Default")
      (node (ref "U$3") (pin "15") (pinfunction "15_RESERVED_15") (pintype "bidirectional"))
    )
    (net (code "120") (name "unconnected-(U$3-16_RESERVED-Pad16)") (class "Default")
      (node (ref "U$3") (pin "16") (pinfunction "16_RESERVED_16") (pintype "bidirectional"))
    )
    (net (code "121") (name "unconnected-(U$3-17_RESERVED-Pad17)") (class "Default")
      (node (ref "U$3") (pin "17") (pinfunction "17_RESERVED_17") (pintype "bidirectional"))
    )
    (net (code "122") (name "unconnected-(U$3-18_SDA{slash}SPI_CS_N-Pad18)") (class "Default")
      (node (ref "U$3") (pin "18") (pinfunction "18_SDA/SPI_CS_N_18") (pintype "bidirectional"))
    )
    (net (code "123") (name "unconnected-(U$3-19_SCL{slash}SPI_CLK-Pad19)") (class "Default")
      (node (ref "U$3") (pin "19") (pinfunction "19_SCL/SPI_CLK_19") (pintype "bidirectional"))
    )
    (net (code "124") (name "unconnected-(U$4-+1-Pad+$2)") (class "Default")
      (node (ref "U$4") (pin "+$2") (pinfunction "+1_+$2") (pintype "passive"))
    )
    (net (code "125") (name "unconnected-(U2-C-Pad5)") (class "Default")
      (node (ref "U2") (pin "5") (pinfunction "C_5") (pintype "input"))
    )
    (net (code "126") (name "unconnected-(U2-D-Pad9)") (class "Default")
      (node (ref "U2") (pin "9") (pinfunction "D_9") (pintype "input"))
    )
    (net (code "127") (name "unconnected-(U2-E-Pad11)") (class "Default")
      (node (ref "U2") (pin "11") (pinfunction "E_11") (pintype "input"))
    )
    (net (code "128") (name "unconnected-(U2-F-Pad13)") (class "Default")
      (node (ref "U2") (pin "13") (pinfunction "F_13") (pintype "input"))
    )
    (net (code "129") (name "unconnected-(U2-I=~{C}-Pad6)") (class "Default")
      (node (ref "U2") (pin "6") (pinfunction "I=~{C}_6") (pintype "output"))
    )
    (net (code "130") (name "unconnected-(U2-J=~{D}-Pad8)") (class "Default")
      (node (ref "U2") (pin "8") (pinfunction "J=~{D}_8") (pintype "output"))
    )
    (net (code "131") (name "unconnected-(U2-K=~{E}-Pad10)") (class "Default")
      (node (ref "U2") (pin "10") (pinfunction "K=~{E}_10") (pintype "output"))
    )
    (net (code "132") (name "unconnected-(U2-L=~{F}-Pad12)") (class "Default")
      (node (ref "U2") (pin "12") (pinfunction "L=~{F}_12") (pintype "output"))
    )
    (net (code "133") (name "unconnected-(U3-D-Pad9)") (class "Default")
      (node (ref "U3") (pin "9") (pinfunction "D_9") (pintype "input"))
    )
    (net (code "134") (name "unconnected-(U3-E-Pad11)") (class "Default")
      (node (ref "U3") (pin "11") (pinfunction "E_11") (pintype "input"))
    )
    (net (code "135") (name "unconnected-(U3-F-Pad14)") (class "Default")
      (node (ref "U3") (pin "14") (pinfunction "F_14") (pintype "input"))
    )
    (net (code "136") (name "unconnected-(U3-J_=~{_D}-Pad10)") (class "Default")
      (node (ref "U3") (pin "10") (pinfunction "J_=~{_D}_10") (pintype "output"))
    )
    (net (code "137") (name "unconnected-(U3-K_=~{_E}-Pad12)") (class "Default")
      (node (ref "U3") (pin "12") (pinfunction "K_=~{_E}_12") (pintype "output"))
    )
    (net (code "138") (name "unconnected-(U3-L_=~{_F}-Pad15)") (class "Default")
      (node (ref "U3") (pin "15") (pinfunction "L_=~{_F}_15") (pintype "output"))
    )
    (net (code "139") (name "unconnected-(U3-NC-Pad16)") (class "Default")
      (node (ref "U3") (pin "16") (pinfunction "NC_16") (pintype "no_connect"))
    )
    (net (code "140") (name "unconnected-(U3-NC_2-Pad13)") (class "Default")
      (node (ref "U3") (pin "13") (pinfunction "NC_2_13") (pintype "no_connect"))
    )
    (net (code "141") (name "unconnected-(U4-{slash}INT-Pad6)") (class "Default")
      (node (ref "U4") (pin "6") (pinfunction "/INT_6") (pintype "output"))
    )
  )
)
